# Microcontroller.net
KiCad netlist of a schematic drawn in Altium Designer
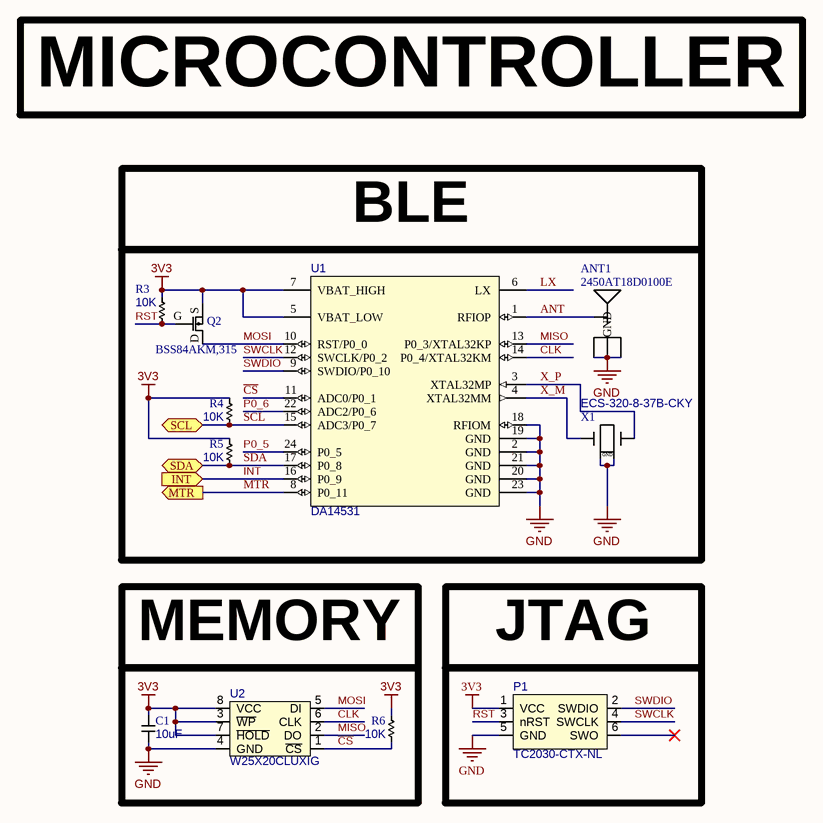
[diagram p0: Microcontroller.SchDoc]

(export (version "E")
  (design (tool "Eeschema 10.0.6"))
  (components
    (comp (ref "ANT1")
      (value "2450AT18D0100E")
      (footprint "2450AT18D0100E_RH")
      (description "2450AT18D0100E 2.4GHz  Chip RF Antenna 2.4GHz ~ 2.5GHz 1.5dBi Solder Surface Mount")
      (libsource (lib "smLib") (part "2450AT18D0100E_RH"))
    )
    (comp (ref "C1")
      (value "10uF")
      (footprint "CAP_0402_HIGH")
      (description "0402 Capacitor")
      (libsource (lib "smLib") (part "Capacitor_0402"))
    )
    (comp (ref "P1")
      (value "TC2030-CTX-NL")
      (footprint "TC2030-CTX-NL")
      (description "TC2030-CTX-NL Tag Connect Cable")
      (libsource (lib "smLib") (part "TC2030-CTX-NL"))
    )
    (comp (ref "Q2")
      (value "BSS84AKM,315")
      (footprint "BSS84AKM,315")
      (description "BSS84AKM,315 MOSFET P-CH 50V SOT883")
      (libsource (lib "smLib") (part "BSS84AKM,315"))
    )
    (comp (ref "R3")
      (value "10K")
      (footprint "RES_0402_HIGH")
      (description "0402 Resistor")
      (libsource (lib "smLib") (part "Resistor_0402"))
    )
    (comp (ref "R4")
      (value "10K")
      (footprint "RES_0402_HIGH")
      (description "0402 Resistor")
      (libsource (lib "smLib") (part "Resistor_0402"))
    )
    (comp (ref "R5")
      (value "10K")
      (footprint "RES_0402_HIGH")
      (description "0402 Resistor")
      (libsource (lib "smLib") (part "Resistor_0402"))
    )
    (comp (ref "R6")
      (value "10K")
      (footprint "RES_0402_HIGH")
      (description "0402 Resistor")
      (libsource (lib "smLib") (part "Resistor_0402"))
    )
    (comp (ref "U1")
      (value "DA14531")
      (footprint "DA14531 QFN")
      (description "DA14531 IC RF TxRx + MCU Bluetooth Bluetooth v5.1 2.4GHz 24-WFQFN, FC")
      (libsource (lib "smLib") (part "DA14531 QFN"))
    )
    (comp (ref "U2")
      (value "W25X20CLUXIG")
      (footprint "W25X20CLUXIG")
      (description "W25X20CLUXIG FLASH Memory IC 2Mb (256K x 8) SPI 104MHz  8-USON (2x3)")
      (libsource (lib "smLib") (part "W25X20CLUXIG"))
    )
    (comp (ref "X1")
      (value "ECS-320-8-37B-CKY")
      (footprint "ECS-320-8-37B-CKY")
      (description "ECS-320-8-37B-CKY CRYSTAL 32.0000MHZ 8PF SMD")
      (libsource (lib "smLib") (part "ECS-320-8-37B-CKY"))
    )
  )
  (nets
    (net (code "1") (name "/ANT") (class "Default")
      (node (ref "ANT1") (pin "1") (pinfunction "FEED_1") (pintype "passive"))
      (node (ref "U1") (pin "1") (pinfunction "RFIOP_1") (pintype "bidirectional"))
    )
    (net (code "2") (name "/CLK") (class "Default")
      (node (ref "U1") (pin "14") (pinfunction "P0_4/XTAL32KM_14") (pintype "bidirectional"))
      (node (ref "U2") (pin "6") (pinfunction "CLK_6") (pintype "passive"))
    )
    (net (code "3") (name "/INT") (class "Default")
      (node (ref "U1") (pin "16") (pinfunction "P0_9_16") (pintype "bidirectional"))
    )
    (net (code "4") (name "/LX") (class "Default")
      (node (ref "U1") (pin "6") (pinfunction "LX_6") (pintype "passive"))
    )
    (net (code "5") (name "/MISO") (class "Default")
      (node (ref "U1") (pin "13") (pinfunction "P0_3/XTAL32KP_13") (pintype "bidirectional"))
      (node (ref "U2") (pin "2") (pinfunction "DO_2") (pintype "passive"))
    )
    (net (code "6") (name "/MOSI") (class "Default")
      (node (ref "Q2") (pin "D") (pinfunction "D_D") (pintype "passive"))
      (node (ref "U1") (pin "10") (pinfunction "RST/P0_0_10") (pintype "bidirectional"))
      (node (ref "U2") (pin "5") (pinfunction "DI_5") (pintype "passive"))
    )
    (net (code "7") (name "/MTR") (class "Default")
      (node (ref "U1") (pin "8") (pinfunction "P0_11_8") (pintype "bidirectional"))
    )
    (net (code "8") (name "/P0_5") (class "Default")
      (node (ref "U1") (pin "24") (pinfunction "P0_5_24") (pintype "bidirectional"))
    )
    (net (code "9") (name "/P0_6") (class "Default")
      (node (ref "U1") (pin "22") (pinfunction "ADC2/P0_6_22") (pintype "bidirectional"))
    )
    (net (code "10") (name "/RST") (class "Default")
      (node (ref "P1") (pin "3") (pinfunction "nRST_3") (pintype "passive"))
      (node (ref "Q2") (pin "G") (pinfunction "G_G") (pintype "passive"))
      (node (ref "R3") (pin "1") (pinfunction "1_1") (pintype "passive"))
    )
    (net (code "11") (name "/SCL") (class "Default")
      (node (ref "R4") (pin "1") (pinfunction "1_1") (pintype "passive"))
      (node (ref "U1") (pin "15") (pinfunction "ADC3/P0_7_15") (pintype "bidirectional"))
    )
    (net (code "12") (name "/SDA") (class "Default")
      (node (ref "R5") (pin "1") (pinfunction "1_1") (pintype "passive"))
      (node (ref "U1") (pin "17") (pinfunction "P0_8_17") (pintype "bidirectional"))
    )
    (net (code "13") (name "/SWCLK") (class "Default")
      (node (ref "P1") (pin "4") (pinfunction "SWCLK_4") (pintype "passive"))
      (node (ref "U1") (pin "12") (pinfunction "SWCLK/P0_2_12") (pintype "bidirectional"))
    )
    (net (code "14") (name "/SWDIO") (class "Default")
      (node (ref "P1") (pin "2") (pinfunction "SWDIO_2") (pintype "passive"))
      (node (ref "U1") (pin "9") (pinfunction "SWDIO/P0_10_9") (pintype "bidirectional"))
    )
    (net (code "15") (name "/X_M") (class "Default")
      (node (ref "U1") (pin "4") (pinfunction "XTAL32MM_4") (pintype "output"))
      (node (ref "X1") (pin "1") (pinfunction "1_1") (pintype "passive"))
    )
    (net (code "16") (name "/X_P") (class "Default")
      (node (ref "U1") (pin "3") (pinfunction "XTAL32MP_3") (pintype "input"))
      (node (ref "X1") (pin "3") (pinfunction "3_3") (pintype "passive"))
    )
    (net (code "17") (name "/~{CS}") (class "Default")
      (node (ref "R6") (pin "1") (pinfunction "1_1") (pintype "passive"))
      (node (ref "U1") (pin "11") (pinfunction "ADC0/P0_1_11") (pintype "bidirectional"))
      (node (ref "U2") (pin "1") (pinfunction "~{CS}_1") (pintype "passive"))
    )
    (net (code "18") (name "3V3") (class "Default")
      (node (ref "C1") (pin "2") (pinfunction "2_2") (pintype "passive"))
      (node (ref "P1") (pin "1") (pinfunction "VCC_1") (pintype "passive"))
      (node (ref "Q2") (pin "S") (pinfunction "S_S") (pintype "passive"))
      (node (ref "R3") (pin "2") (pinfunction "2_2") (pintype "passive"))
      (node (ref "R4") (pin "2") (pinfunction "2_2") (pintype "passive"))
      (node (ref "R5") (pin "2") (pinfunction "2_2") (pintype "passive"))
      (node (ref "R6") (pin "2") (pinfunction "2_2") (pintype "passive"))
      (node (ref "U1") (pin "5") (pinfunction "VBAT_LOW_5") (pintype "power_in"))
      (node (ref "U1") (pin "7") (pinfunction "VBAT_HIGH_7") (pintype "power_in"))
      (node (ref "U2") (pin "3") (pinfunction "~{WP}_3") (pintype "passive"))
      (node (ref "U2") (pin "7") (pinfunction "~{HOLD}_7") (pintype "passive"))
      (node (ref "U2") (pin "8") (pinfunction "VCC_8") (pintype "passive"))
    )
    (net (code "19") (name "GND") (class "Default")
      (node (ref "ANT1") (pin "2") (pinfunction "GND_2") (pintype "passive"))
      (node (ref "ANT1") (pin "3") (pinfunction "GND_3") (pintype "passive"))
      (node (ref "ANT1") (pin "4") (pinfunction "GND_4") (pintype "passive"))
      (node (ref "C1") (pin "1") (pinfunction "1_1") (pintype "passive"))
      (node (ref "P1") (pin "5") (pinfunction "GND_5") (pintype "passive"))
      (node (ref "U1") (pin "18") (pinfunction "RFIOM_18") (pintype "bidirectional"))
      (node (ref "U1") (pin "19") (pinfunction "GND_19") (pintype "power_in"))
      (node (ref "U1") (pin "2") (pinfunction "GND_2") (pintype "power_in"))
      (node (ref "U1") (pin "20") (pinfunction "GND_20") (pintype "power_in"))
      (node (ref "U1") (pin "21") (pinfunction "GND_21") (pintype "power_in"))
      (node (ref "U1") (pin "23") (pinfunction "GND_23") (pintype "power_in"))
      (node (ref "U2") (pin "4") (pinfunction "GND_4") (pintype "passive"))
      (node (ref "X1") (pin "2") (pinfunction "2_2") (pintype "passive"))
      (node (ref "X1") (pin "4") (pinfunction "GND_4") (pintype "passive"))
    )
    (net (code "20") (name "unconnected-(P1-SWO-Pad6)") (class "Default")
      (node (ref "P1") (pin "6") (pinfunction "SWO_6") (pintype "passive+no_connect"))
    )
  )
)
